# Charge_Interface.net
KiCad netlist of a schematic drawn in Altium Designer
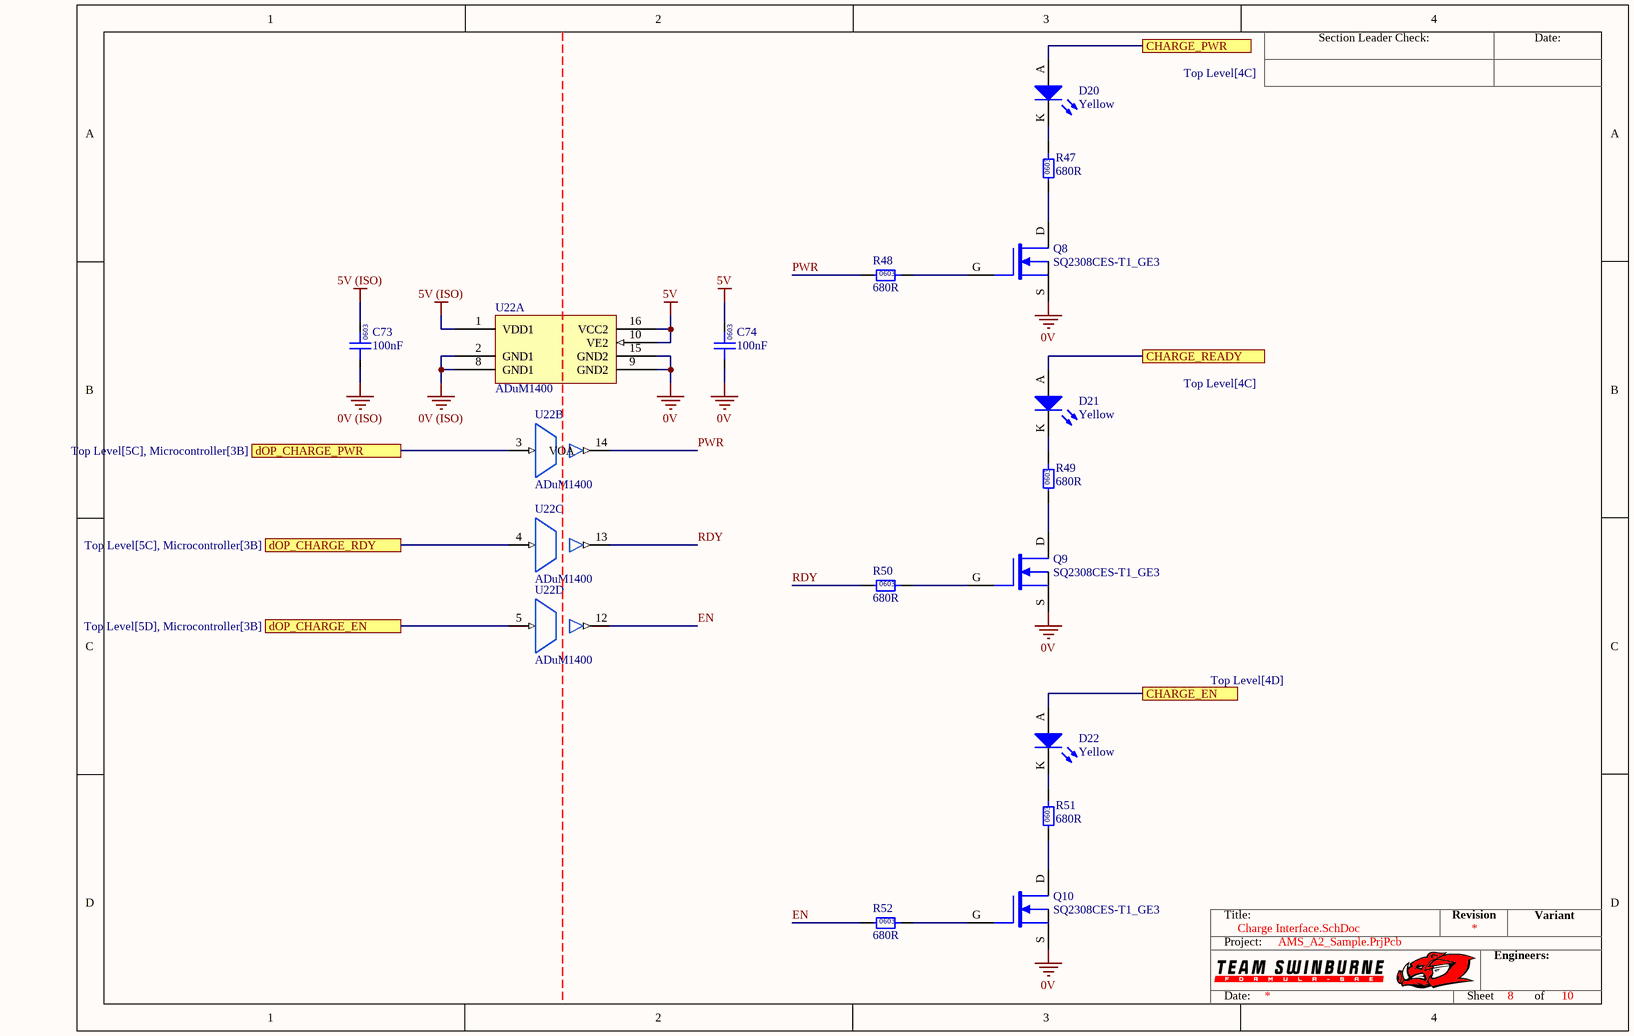
[diagram p0: Charge Interface.SchDoc]

(export (version "E")
  (design (tool "Eeschema 10.0.6"))
  (components
    (comp (ref "C73")
      (value "100nF")
      (footprint "0603")
      (fields
        (field (name "PART NUMBER") "GCM188L81H104KA57D")
        (field (name "MANUFACTURER") "muRata")
        (field (name "TOLERANCE") "±10%")
      )
      (libsource (lib "ts_standard_library") (part "Capacitor 0603"))
    )
    (comp (ref "C74")
      (value "100nF")
      (footprint "0603")
      (fields
        (field (name "PART NUMBER") "GCM188L81H104KA57D")
        (field (name "MANUFACTURER") "muRata")
        (field (name "TOLERANCE") "±10%")
      )
      (libsource (lib "ts_standard_library") (part "Capacitor 0603"))
    )
    (comp (ref "D20")
      (value "Yellow")
      (footprint "0805 LED")
      (description "Yellow LED Indication - Discrete 1.75V 0805 (2012 Metric)")
      (fields (field (name "PART NUMBER") "SML-211YTT86") (field (name "MANUFACTURER") "ROHM Semiconductor"))
      (libsource (lib "ts_standard_library") (part "LED"))
    )
    (comp (ref "D21")
      (value "Yellow")
      (footprint "0805 LED")
      (description "Yellow LED Indication - Discrete 1.75V 0805 (2012 Metric)")
      (fields (field (name "PART NUMBER") "SML-211YTT86") (field (name "MANUFACTURER") "ROHM Semiconductor"))
      (libsource (lib "ts_standard_library") (part "LED"))
    )
    (comp (ref "D22")
      (value "Yellow")
      (footprint "0805 LED")
      (description "Yellow LED Indication - Discrete 1.75V 0805 (2012 Metric)")
      (fields (field (name "PART NUMBER") "SML-211YTT86") (field (name "MANUFACTURER") "ROHM Semiconductor"))
      (libsource (lib "ts_standard_library") (part "LED"))
    )
    (comp (ref "Q8")
      (value "SQ2308CES-T1_GE3")
      (footprint "VSHY SOT-23-3")
      (description "MOSFET N-CH 60V 2.3A SOT23")
      (fields
        (field (name "MANUFACTURER") "Vishay Siliconix")
        (field (name "DIGIKEY PART NUMBER") "SQ2308CES-T1_GE3CT-ND")
        (field (name "PUBLISHER") "Altium Limited")
      )
      (libsource (lib "ts_standard_library") (part "MOSFET-N"))
    )
    (comp (ref "Q9")
      (value "SQ2308CES-T1_GE3")
      (footprint "VSHY SOT-23-3")
      (description "MOSFET N-CH 60V 2.3A SOT23")
      (fields
        (field (name "MANUFACTURER") "Vishay Siliconix")
        (field (name "DIGIKEY PART NUMBER") "SQ2308CES-T1_GE3CT-ND")
        (field (name "PUBLISHER") "Altium Limited")
      )
      (libsource (lib "ts_standard_library") (part "MOSFET-N"))
    )
    (comp (ref "Q10")
      (value "SQ2308CES-T1_GE3")
      (footprint "VSHY SOT-23-3")
      (description "MOSFET N-CH 60V 2.3A SOT23")
      (fields
        (field (name "MANUFACTURER") "Vishay Siliconix")
        (field (name "DIGIKEY PART NUMBER") "SQ2308CES-T1_GE3CT-ND")
        (field (name "PUBLISHER") "Altium Limited")
      )
      (libsource (lib "ts_standard_library") (part "MOSFET-N"))
    )
    (comp (ref "R47")
      (value "680R")
      (footprint "0603")
      (fields
        (field (name "PART NUMBER") "RC0603JR-13680RL")
        (field (name "MANUFACTURER") "YAGEO")
        (field (name "TOLERANCE") "0.01")
      )
      (libsource (lib "ts_standard_library") (part "Resistor 0603"))
    )
    (comp (ref "R48")
      (value "680R")
      (footprint "0603")
      (fields
        (field (name "PART NUMBER") "RC0603JR-13680RL")
        (field (name "MANUFACTURER") "YAGEO")
        (field (name "TOLERANCE") "0.01")
      )
      (libsource (lib "ts_standard_library") (part "Resistor 0603"))
    )
    (comp (ref "R49")
      (value "680R")
      (footprint "0603")
      (fields
        (field (name "PART NUMBER") "RC0603JR-13680RL")
        (field (name "MANUFACTURER") "YAGEO")
        (field (name "TOLERANCE") "0.01")
      )
      (libsource (lib "ts_standard_library") (part "Resistor 0603"))
    )
    (comp (ref "R50")
      (value "680R")
      (footprint "0603")
      (fields
        (field (name "PART NUMBER") "RC0603JR-13680RL")
        (field (name "MANUFACTURER") "YAGEO")
        (field (name "TOLERANCE") "0.01")
      )
      (libsource (lib "ts_standard_library") (part "Resistor 0603"))
    )
    (comp (ref "R51")
      (value "680R")
      (footprint "0603")
      (fields
        (field (name "PART NUMBER") "RC0603JR-13680RL")
        (field (name "MANUFACTURER") "YAGEO")
        (field (name "TOLERANCE") "0.01")
      )
      (libsource (lib "ts_standard_library") (part "Resistor 0603"))
    )
    (comp (ref "R52")
      (value "680R")
      (footprint "0603")
      (fields
        (field (name "PART NUMBER") "RC0603JR-13680RL")
        (field (name "MANUFACTURER") "YAGEO")
        (field (name "TOLERANCE") "0.01")
      )
      (libsource (lib "ts_standard_library") (part "Resistor 0603"))
    )
    (comp (ref "U22")
      (value "ADuM1400")
      (footprint "AD 16-SOIC")
      (fields
        (field (name "MANUFACTURER") "Analog Devices")
        (field (name "DIGIKEY PART NUMBER") "ADUM1400WSRWZ-ND")
      )
      (libsource (lib "ts_standard_library") (part "ADuM1400"))
    )
  )
  (nets
    (net (code "1") (name "/CHARGE_EN") (class "Default")
      (node (ref "D22") (pin "A") (pinfunction "A_A") (pintype "passive"))
    )
    (net (code "2") (name "/CHARGE_PWR") (class "Default")
      (node (ref "D20") (pin "A") (pinfunction "A_A") (pintype "passive"))
    )
    (net (code "3") (name "/CHARGE_READY") (class "Default")
      (node (ref "D21") (pin "A") (pinfunction "A_A") (pintype "passive"))
    )
    (net (code "4") (name "/EN") (class "Default")
      (node (ref "R52") (pin "1") (pinfunction "1_1") (pintype "passive"))
      (node (ref "U22") (pin "12") (pinfunction "VOC_12") (pintype "output"))
    )
    (net (code "5") (name "/PWR") (class "Default")
      (node (ref "R48") (pin "1") (pinfunction "1_1") (pintype "passive"))
      (node (ref "U22") (pin "14") (pinfunction "VOA_14") (pintype "output"))
    )
    (net (code "6") (name "/RDY") (class "Default")
      (node (ref "R50") (pin "1") (pinfunction "1_1") (pintype "passive"))
      (node (ref "U22") (pin "13") (pinfunction "VOB_13") (pintype "output"))
    )
    (net (code "7") (name "/dOP_CHARGE_EN") (class "Default")
      (node (ref "U22") (pin "5") (pinfunction "VIC_5") (pintype "input"))
    )
    (net (code "8") (name "/dOP_CHARGE_PWR") (class "Default")
      (node (ref "U22") (pin "3") (pinfunction "VIA_3") (pintype "input"))
    )
    (net (code "9") (name "/dOP_CHARGE_RDY") (class "Default")
      (node (ref "U22") (pin "4") (pinfunction "VIB_4") (pintype "input"))
    )
    (net (code "10") (name "0V") (class "Default")
      (node (ref "C74") (pin "1") (pinfunction "1_1") (pintype "passive"))
      (node (ref "Q10") (pin "S") (pinfunction "S_S") (pintype "passive"))
      (node (ref "Q8") (pin "S") (pinfunction "S_S") (pintype "passive"))
      (node (ref "Q9") (pin "S") (pinfunction "S_S") (pintype "passive"))
      (node (ref "U22") (pin "15") (pinfunction "GND2_15") (pintype "power_in"))
      (node (ref "U22") (pin "9") (pinfunction "GND2_9") (pintype "power_in"))
    )
    (net (code "11") (name "0V (ISO)") (class "Default")
      (node (ref "C73") (pin "1") (pinfunction "1_1") (pintype "passive"))
      (node (ref "U22") (pin "2") (pinfunction "GND1_2") (pintype "power_in"))
      (node (ref "U22") (pin "8") (pinfunction "GND1_8") (pintype "power_in"))
    )
    (net (code "12") (name "5V") (class "Default")
      (node (ref "C74") (pin "2") (pinfunction "2_2") (pintype "passive"))
      (node (ref "U22") (pin "10") (pinfunction "VE2_10") (pintype "input"))
      (node (ref "U22") (pin "16") (pinfunction "VCC2_16") (pintype "power_in"))
    )
    (net (code "13") (name "5V (ISO)") (class "Default")
      (node (ref "C73") (pin "2") (pinfunction "2_2") (pintype "passive"))
      (node (ref "U22") (pin "1") (pinfunction "VDD1_1") (pintype "power_in"))
    )
    (net (code "14") (name "Net-(D20-PadK)") (class "Default")
      (node (ref "D20") (pin "K") (pinfunction "K_K") (pintype "passive"))
      (node (ref "R47") (pin "2") (pinfunction "2_2") (pintype "passive"))
    )
    (net (code "15") (name "Net-(D21-PadK)") (class "Default")
      (node (ref "D21") (pin "K") (pinfunction "K_K") (pintype "passive"))
      (node (ref "R49") (pin "2") (pinfunction "2_2") (pintype "passive"))
    )
    (net (code "16") (name "Net-(D22-PadK)") (class "Default")
      (node (ref "D22") (pin "K") (pinfunction "K_K") (pintype "passive"))
      (node (ref "R51") (pin "2") (pinfunction "2_2") (pintype "passive"))
    )
    (net (code "17") (name "Net-(Q8-PadD)") (class "Default")
      (node (ref "Q8") (pin "D") (pinfunction "D_D") (pintype "passive"))
      (node (ref "R47") (pin "1") (pinfunction "1_1") (pintype "passive"))
    )
    (net (code "18") (name "Net-(Q8-PadG)") (class "Default")
      (node (ref "Q8") (pin "G") (pinfunction "G_G") (pintype "passive"))
      (node (ref "R48") (pin "2") (pinfunction "2_2") (pintype "passive"))
    )
    (net (code "19") (name "Net-(Q9-PadD)") (class "Default")
      (node (ref "Q9") (pin "D") (pinfunction "D_D") (pintype "passive"))
      (node (ref "R49") (pin "1") (pinfunction "1_1") (pintype "passive"))
    )
    (net (code "20") (name "Net-(Q9-PadG)") (class "Default")
      (node (ref "Q9") (pin "G") (pinfunction "G_G") (pintype "passive"))
      (node (ref "R50") (pin "2") (pinfunction "2_2") (pintype "passive"))
    )
    (net (code "21") (name "Net-(Q10-PadD)") (class "Default")
      (node (ref "Q10") (pin "D") (pinfunction "D_D") (pintype "passive"))
      (node (ref "R51") (pin "1") (pinfunction "1_1") (pintype "passive"))
    )
    (net (code "22") (name "Net-(Q10-PadG)") (class "Default")
      (node (ref "Q10") (pin "G") (pinfunction "G_G") (pintype "passive"))
      (node (ref "R52") (pin "2") (pinfunction "2_2") (pintype "passive"))
    )
  )
)
